# ESC.net
KiCad netlist of a schematic drawn in Altium Designer
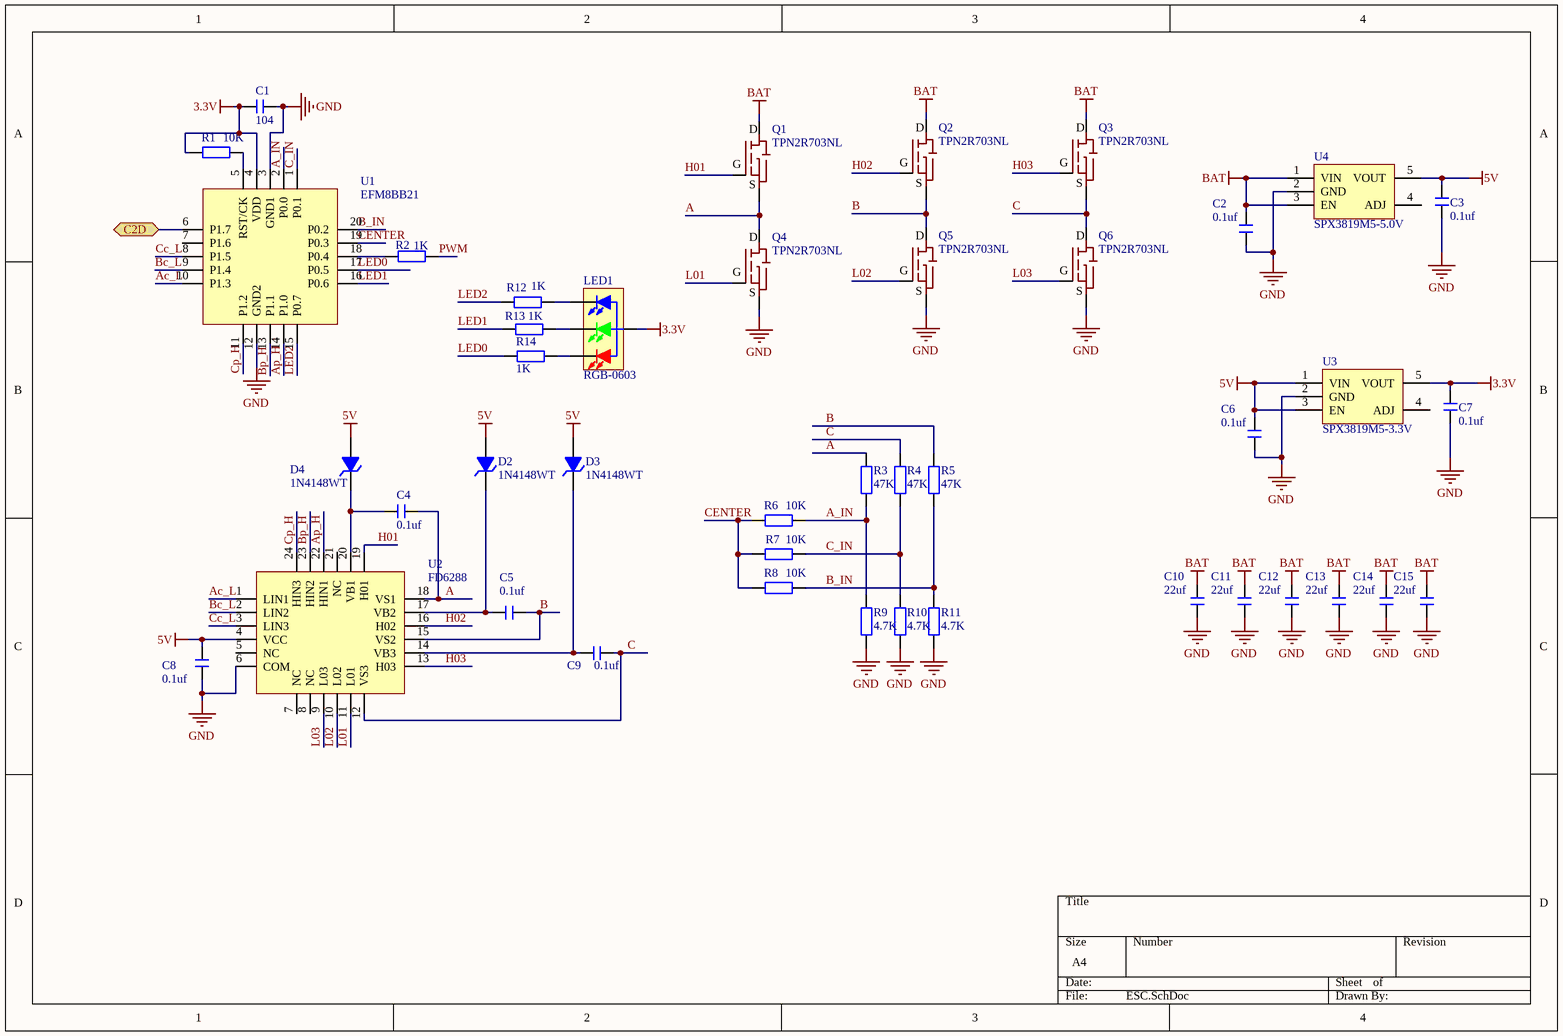
[diagram p0: ESC.SchDoc]

(export (version "E")
  (design (tool "Eeschema 10.0.6"))
  (components
    (comp (ref "C1")
      (value "104")
      (footprint "0402-C-1.6*0.5")
      (description "无极性贴片电容")
      (fields (field (name "版权归属") "源创客"))
      (libsource (lib "3.1   - 电阻-电容-电感") (part "C"))
    )
    (comp (ref "C2") (value "0.1uf") (footprint "0402-C-1.6*0.5") (libsource (lib "L-电阻电容电感") (part "C")))
    (comp (ref "C3") (value "0.1uf") (footprint "0402-C-1.6*0.5") (libsource (lib "L-电阻电容电感") (part "C")))
    (comp (ref "C4") (value "0.1uf") (footprint "0402-C-1.6*0.5") (libsource (lib "L-电阻电容电感") (part "C")))
    (comp (ref "C5") (value "0.1uf") (footprint "0402-C-1.6*0.5") (libsource (lib "L-电阻电容电感") (part "C")))
    (comp (ref "C6") (value "0.1uf") (footprint "0402-C-1.6*0.5") (libsource (lib "L-电阻电容电感") (part "C")))
    (comp (ref "C7") (value "0.1uf") (footprint "0402-C-1.6*0.5") (libsource (lib "L-电阻电容电感") (part "C")))
    (comp (ref "C8") (value "0.1uf") (footprint "0402-C-1.6*0.5") (libsource (lib "L-电阻电容电感") (part "C")))
    (comp (ref "C9") (value "0.1uf") (footprint "0402-C-1.6*0.5") (libsource (lib "L-电阻电容电感") (part "C")))
    (comp (ref "C10") (value "22uf") (footprint "0805-C-3.0*1.4") (libsource (lib "L-电阻电容电感") (part "C")))
    (comp (ref "C11") (value "22uf") (footprint "0805-C-3.0*1.4") (libsource (lib "L-电阻电容电感") (part "C")))
    (comp (ref "C12") (value "22uf") (footprint "0805-C-3.0*1.4") (libsource (lib "L-电阻电容电感") (part "C")))
    (comp (ref "C13") (value "22uf") (footprint "0805-C-3.0*1.4") (libsource (lib "L-电阻电容电感") (part "C")))
    (comp (ref "C14") (value "22uf") (footprint "0805-C-3.0*1.4") (libsource (lib "L-电阻电容电感") (part "C")))
    (comp (ref "C15") (value "22uf") (footprint "0805-C-3.0*1.4") (libsource (lib "L-电阻电容电感") (part "C")))
    (comp (ref "D2")
      (value "1N4148WT")
      (footprint "L_SOD523")
      (libsource (lib "L-二极管、稳压管") (part "1N4148WT"))
    )
    (comp (ref "D3")
      (value "1N4148WT")
      (footprint "L_SOD523")
      (libsource (lib "L-二极管、稳压管") (part "1N4148WT"))
    )
    (comp (ref "D4")
      (value "1N4148WT")
      (footprint "L_SOD523")
      (libsource (lib "L-二极管、稳压管") (part "1N4148WT"))
    )
    (comp (ref "LED1")
      (value "RGB-0603")
      (footprint "LC-0603_Rx2")
      (description "三基色LED")
      (fields (field (name "版权归属") "源创客"))
      (libsource (lib "9.1   - LED") (part "LED-RGB-3528"))
    )
    (comp (ref "Q1")
      (value "TPN2R703NL")
      (footprint "8-PowerVDFN")
      (libsource (lib "L-MOSFET") (part "TPN2R703NL"))
    )
    (comp (ref "Q2")
      (value "TPN2R703NL")
      (footprint "8-PowerVDFN")
      (libsource (lib "L-MOSFET") (part "TPN2R703NL"))
    )
    (comp (ref "Q3")
      (value "TPN2R703NL")
      (footprint "8-PowerVDFN")
      (libsource (lib "L-MOSFET") (part "TPN2R703NL"))
    )
    (comp (ref "Q4")
      (value "TPN2R703NL")
      (footprint "8-PowerVDFN")
      (libsource (lib "L-MOSFET") (part "TPN2R703NL"))
    )
    (comp (ref "Q5")
      (value "TPN2R703NL")
      (footprint "8-PowerVDFN")
      (libsource (lib "L-MOSFET") (part "TPN2R703NL"))
    )
    (comp (ref "Q6")
      (value "TPN2R703NL")
      (footprint "8-PowerVDFN")
      (libsource (lib "L-MOSFET") (part "TPN2R703NL"))
    )
    (comp (ref "R1") (value "10K") (footprint "0402-R-1.6*0.5") (libsource (lib "L-电阻电容电感") (part "R")))
    (comp (ref "R2")
      (value "1K")
      (footprint "0402-R-1.6*0.5")
      (description "贴片电阻")
      (fields (field (name "版权归属") "源创客"))
      (libsource (lib "3.1   - 电阻-电容-电感") (part "R"))
    )
    (comp (ref "R3") (value "47K") (footprint "0402-R-1.6*0.5") (libsource (lib "L-电阻电容电感") (part "R")))
    (comp (ref "R4") (value "47K") (footprint "0402-R-1.6*0.5") (libsource (lib "L-电阻电容电感") (part "R")))
    (comp (ref "R5") (value "47K") (footprint "0402-R-1.6*0.5") (libsource (lib "L-电阻电容电感") (part "R")))
    (comp (ref "R6") (value "10K") (footprint "0402-R-1.6*0.5") (libsource (lib "L-电阻电容电感") (part "R")))
    (comp (ref "R7") (value "10K") (footprint "0402-R-1.6*0.5") (libsource (lib "L-电阻电容电感") (part "R")))
    (comp (ref "R8") (value "10K") (footprint "0402-R-1.6*0.5") (libsource (lib "L-电阻电容电感") (part "R")))
    (comp (ref "R9") (value "4.7K") (footprint "0402-R-1.6*0.5") (libsource (lib "L-电阻电容电感") (part "R")))
    (comp (ref "R10") (value "4.7K") (footprint "0402-R-1.6*0.5") (libsource (lib "L-电阻电容电感") (part "R")))
    (comp (ref "R11") (value "4.7K") (footprint "0402-R-1.6*0.5") (libsource (lib "L-电阻电容电感") (part "R")))
    (comp (ref "R12") (value "1K") (footprint "0402-R-1.6*0.5") (libsource (lib "PCB_Project3") (part "R")))
    (comp (ref "R13") (value "1K") (footprint "0402-R-1.6*0.5") (libsource (lib "PCB_Project3") (part "R")))
    (comp (ref "R14") (value "1K") (footprint "0402-R-1.6*0.5") (libsource (lib "PCB_Project3") (part "R")))
    (comp (ref "U1")
      (value "EFM8BB21")
      (footprint "EFM8BB21F16G-C-QFN20")
      (libsource (lib "PCB_Project3") (part "EFM8BB21"))
    )
    (comp (ref "U2")
      (value "FD6288")
      (footprint "LC-QFN-24_4x4x05P")
      (libsource (lib "PCB_Project3") (part "FD6288"))
    )
    (comp (ref "U3")
      (value "SPX3819M5-3.3V")
      (footprint "L - SOT23-5L")
      (fields (field (name "版权所有") "Ly"))
      (libsource (lib "L-电源芯片") (part "SPX3819M5"))
    )
    (comp (ref "U4")
      (value "SPX3819M5-5.0V")
      (footprint "L - SOT23-5L")
      (fields (field (name "版权所有") "Ly"))
      (libsource (lib "L-电源芯片") (part "SPX3819M5"))
    )
  )
  (nets
    (net (code "1") (name "/A") (class "Default")
      (node (ref "C4") (pin "2") (pinfunction "2_2") (pintype "passive"))
      (node (ref "Q1") (pin "1") (pinfunction "1_1") (pintype "passive"))
      (node (ref "Q4") (pin "3") (pinfunction "3_3") (pintype "passive"))
      (node (ref "R3") (pin "1") (pinfunction "1_1") (pintype "passive"))
      (node (ref "U2") (pin "18") (pinfunction "VS1_18") (pintype "passive"))
    )
    (net (code "2") (name "/A_IN") (class "Default")
      (node (ref "R3") (pin "2") (pinfunction "2_2") (pintype "passive"))
      (node (ref "R6") (pin "2") (pinfunction "2_2") (pintype "passive"))
      (node (ref "R9") (pin "1") (pinfunction "1_1") (pintype "passive"))
      (node (ref "U1") (pin "2") (pinfunction "P0.0_2") (pintype "passive"))
    )
    (net (code "3") (name "/Ac_L") (class "Default")
      (node (ref "U1") (pin "10") (pinfunction "P1.3_10") (pintype "passive"))
      (node (ref "U2") (pin "1") (pinfunction "LIN1_1") (pintype "passive"))
    )
    (net (code "4") (name "/Ap_H") (class "Default")
      (node (ref "U1") (pin "14") (pinfunction "P1.0_14") (pintype "passive"))
      (node (ref "U2") (pin "22") (pinfunction "HIN1_22") (pintype "passive"))
    )
    (net (code "5") (name "/B") (class "Default")
      (node (ref "C5") (pin "2") (pinfunction "2_2") (pintype "passive"))
      (node (ref "Q2") (pin "1") (pinfunction "1_1") (pintype "passive"))
      (node (ref "Q5") (pin "3") (pinfunction "3_3") (pintype "passive"))
      (node (ref "R5") (pin "1") (pinfunction "1_1") (pintype "passive"))
      (node (ref "U2") (pin "15") (pinfunction "VS2_15") (pintype "passive"))
    )
    (net (code "6") (name "/B_IN") (class "Default")
      (node (ref "R11") (pin "1") (pinfunction "1_1") (pintype "passive"))
      (node (ref "R5") (pin "2") (pinfunction "2_2") (pintype "passive"))
      (node (ref "R8") (pin "2") (pinfunction "2_2") (pintype "passive"))
      (node (ref "U1") (pin "20") (pinfunction "P0.2_20") (pintype "passive"))
    )
    (net (code "7") (name "/Bc_L") (class "Default")
      (node (ref "U1") (pin "9") (pinfunction "P1.4_9") (pintype "passive"))
      (node (ref "U2") (pin "2") (pinfunction "LIN2_2") (pintype "passive"))
    )
    (net (code "8") (name "/Bp_H") (class "Default")
      (node (ref "U1") (pin "13") (pinfunction "P1.1_13") (pintype "passive"))
      (node (ref "U2") (pin "23") (pinfunction "HIN2_23") (pintype "passive"))
    )
    (net (code "9") (name "/C") (class "Default")
      (node (ref "C9") (pin "2") (pinfunction "2_2") (pintype "passive"))
      (node (ref "Q3") (pin "1") (pinfunction "1_1") (pintype "passive"))
      (node (ref "Q6") (pin "3") (pinfunction "3_3") (pintype "passive"))
      (node (ref "R4") (pin "1") (pinfunction "1_1") (pintype "passive"))
      (node (ref "U2") (pin "12") (pinfunction "VS3_12") (pintype "passive"))
    )
    (net (code "10") (name "/C2D") (class "Default")
      (node (ref "U1") (pin "6") (pinfunction "P1.7_6") (pintype "passive"))
    )
    (net (code "11") (name "/CENTER") (class "Default")
      (node (ref "R6") (pin "1") (pinfunction "1_1") (pintype "passive"))
      (node (ref "R7") (pin "1") (pinfunction "1_1") (pintype "passive"))
      (node (ref "R8") (pin "1") (pinfunction "1_1") (pintype "passive"))
      (node (ref "U1") (pin "19") (pinfunction "P0.3_19") (pintype "passive"))
    )
    (net (code "12") (name "/C_IN") (class "Default")
      (node (ref "R10") (pin "1") (pinfunction "1_1") (pintype "passive"))
      (node (ref "R4") (pin "2") (pinfunction "2_2") (pintype "passive"))
      (node (ref "R7") (pin "2") (pinfunction "2_2") (pintype "passive"))
      (node (ref "U1") (pin "1") (pinfunction "P0.1_1") (pintype "passive"))
    )
    (net (code "13") (name "/Cc_L") (class "Default")
      (node (ref "U1") (pin "8") (pinfunction "P1.5_8") (pintype "passive"))
      (node (ref "U2") (pin "3") (pinfunction "LIN3_3") (pintype "passive"))
    )
    (net (code "14") (name "/Cp_H") (class "Default")
      (node (ref "U1") (pin "11") (pinfunction "P1.2_11") (pintype "passive"))
      (node (ref "U2") (pin "24") (pinfunction "HIN3_24") (pintype "passive"))
    )
    (net (code "15") (name "/H01") (class "Default")
      (node (ref "Q1") (pin "2") (pinfunction "2_2") (pintype "passive"))
      (node (ref "U2") (pin "19") (pinfunction "H01_19") (pintype "passive"))
    )
    (net (code "16") (name "/H02") (class "Default")
      (node (ref "Q2") (pin "2") (pinfunction "2_2") (pintype "passive"))
      (node (ref "U2") (pin "16") (pinfunction "H02_16") (pintype "passive"))
    )
    (net (code "17") (name "/H03") (class "Default")
      (node (ref "Q3") (pin "2") (pinfunction "2_2") (pintype "passive"))
      (node (ref "U2") (pin "13") (pinfunction "H03_13") (pintype "passive"))
    )
    (net (code "18") (name "/L01") (class "Default")
      (node (ref "Q4") (pin "2") (pinfunction "2_2") (pintype "passive"))
      (node (ref "U2") (pin "11") (pinfunction "L01_11") (pintype "passive"))
    )
    (net (code "19") (name "/L02") (class "Default")
      (node (ref "Q5") (pin "2") (pinfunction "2_2") (pintype "passive"))
      (node (ref "U2") (pin "10") (pinfunction "L02_10") (pintype "passive"))
    )
    (net (code "20") (name "/L03") (class "Default")
      (node (ref "Q6") (pin "2") (pinfunction "2_2") (pintype "passive"))
      (node (ref "U2") (pin "9") (pinfunction "L03_9") (pintype "passive"))
    )
    (net (code "21") (name "/LED0") (class "Default")
      (node (ref "R14") (pin "1") (pinfunction "1_1") (pintype "passive"))
      (node (ref "U1") (pin "17") (pinfunction "P0.5_17") (pintype "passive"))
    )
    (net (code "22") (name "/LED1") (class "Default")
      (node (ref "R13") (pin "1") (pinfunction "1_1") (pintype "passive"))
      (node (ref "U1") (pin "16") (pinfunction "P0.6_16") (pintype "passive"))
    )
    (net (code "23") (name "/LED2") (class "Default")
      (node (ref "R12") (pin "1") (pinfunction "1_1") (pintype "passive"))
      (node (ref "U1") (pin "15") (pinfunction "P0.7_15") (pintype "passive"))
    )
    (net (code "24") (name "/PWM") (class "Default")
      (node (ref "R2") (pin "1") (pinfunction "1_1") (pintype "passive"))
    )
    (net (code "25") (name "3.3V") (class "Default")
      (node (ref "C1") (pin "2") (pinfunction "2_2") (pintype "passive"))
      (node (ref "C7") (pin "2") (pinfunction "2_2") (pintype "passive"))
      (node (ref "LED1") (pin "4") (pinfunction "A_4") (pintype "passive"))
      (node (ref "R1") (pin "1") (pinfunction "1_1") (pintype "passive"))
      (node (ref "U1") (pin "4") (pinfunction "VDD_4") (pintype "passive"))
      (node (ref "U3") (pin "5") (pinfunction "VOUT_5") (pintype "passive"))
    )
    (net (code "26") (name "5V") (class "Default")
      (node (ref "C3") (pin "2") (pinfunction "2_2") (pintype "passive"))
      (node (ref "C6") (pin "2") (pinfunction "2_2") (pintype "passive"))
      (node (ref "C8") (pin "2") (pinfunction "2_2") (pintype "passive"))
      (node (ref "D2") (pin "1") (pinfunction "A_1") (pintype "passive"))
      (node (ref "D3") (pin "1") (pinfunction "A_1") (pintype "passive"))
      (node (ref "D4") (pin "1") (pinfunction "A_1") (pintype "passive"))
      (node (ref "U2") (pin "4") (pinfunction "VCC_4") (pintype "passive"))
      (node (ref "U3") (pin "1") (pinfunction "VIN_1") (pintype "passive"))
      (node (ref "U3") (pin "3") (pinfunction "EN_3") (pintype "passive"))
      (node (ref "U4") (pin "5") (pinfunction "VOUT_5") (pintype "passive"))
    )
    (net (code "27") (name "BAT") (class "Default")
      (node (ref "C10") (pin "2") (pinfunction "2_2") (pintype "passive"))
      (node (ref "C11") (pin "2") (pinfunction "2_2") (pintype "passive"))
      (node (ref "C12") (pin "2") (pinfunction "2_2") (pintype "passive"))
      (node (ref "C13") (pin "2") (pinfunction "2_2") (pintype "passive"))
      (node (ref "C14") (pin "2") (pinfunction "2_2") (pintype "passive"))
      (node (ref "C15") (pin "2") (pinfunction "2_2") (pintype "passive"))
      (node (ref "C2") (pin "2") (pinfunction "2_2") (pintype "passive"))
      (node (ref "Q1") (pin "3") (pinfunction "3_3") (pintype "passive"))
      (node (ref "Q2") (pin "3") (pinfunction "3_3") (pintype "passive"))
      (node (ref "Q3") (pin "3") (pinfunction "3_3") (pintype "passive"))
      (node (ref "U4") (pin "1") (pinfunction "VIN_1") (pintype "passive"))
      (node (ref "U4") (pin "3") (pinfunction "EN_3") (pintype "passive"))
    )
    (net (code "28") (name "GND") (class "Default")
      (node (ref "C1") (pin "1") (pinfunction "1_1") (pintype "passive"))
      (node (ref "C10") (pin "1") (pinfunction "1_1") (pintype "passive"))
      (node (ref "C11") (pin "1") (pinfunction "1_1") (pintype "passive"))
      (node (ref "C12") (pin "1") (pinfunction "1_1") (pintype "passive"))
      (node (ref "C13") (pin "1") (pinfunction "1_1") (pintype "passive"))
      (node (ref "C14") (pin "1") (pinfunction "1_1") (pintype "passive"))
      (node (ref "C15") (pin "1") (pinfunction "1_1") (pintype "passive"))
      (node (ref "C2") (pin "1") (pinfunction "1_1") (pintype "passive"))
      (node (ref "C3") (pin "1") (pinfunction "1_1") (pintype "passive"))
      (node (ref "C6") (pin "1") (pinfunction "1_1") (pintype "passive"))
      (node (ref "C7") (pin "1") (pinfunction "1_1") (pintype "passive"))
      (node (ref "C8") (pin "1") (pinfunction "1_1") (pintype "passive"))
      (node (ref "Q4") (pin "1") (pinfunction "1_1") (pintype "passive"))
      (node (ref "Q5") (pin "1") (pinfunction "1_1") (pintype "passive"))
      (node (ref "Q6") (pin "1") (pinfunction "1_1") (pintype "passive"))
      (node (ref "R10") (pin "2") (pinfunction "2_2") (pintype "passive"))
      (node (ref "R11") (pin "2") (pinfunction "2_2") (pintype "passive"))
      (node (ref "R9") (pin "2") (pinfunction "2_2") (pintype "passive"))
      (node (ref "U1") (pin "12") (pinfunction "GND2_12") (pintype "passive"))
      (node (ref "U1") (pin "3") (pinfunction "GND1_3") (pintype "passive"))
      (node (ref "U2") (pin "6") (pinfunction "COM_6") (pintype "passive"))
      (node (ref "U3") (pin "2") (pinfunction "GND_2") (pintype "passive"))
      (node (ref "U4") (pin "2") (pinfunction "GND_2") (pintype "passive"))
    )
    (net (code "29") (name "Net-(D2-K)") (class "Default")
      (node (ref "C5") (pin "1") (pinfunction "1_1") (pintype "passive"))
      (node (ref "D2") (pin "2") (pinfunction "K_2") (pintype "passive"))
      (node (ref "U2") (pin "17") (pinfunction "VB2_17") (pintype "passive"))
    )
    (net (code "30") (name "Net-(D3-K)") (class "Default")
      (node (ref "C9") (pin "1") (pinfunction "1_1") (pintype "passive"))
      (node (ref "D3") (pin "2") (pinfunction "K_2") (pintype "passive"))
      (node (ref "U2") (pin "14") (pinfunction "VB3_14") (pintype "passive"))
    )
    (net (code "31") (name "Net-(D4-K)") (class "Default")
      (node (ref "C4") (pin "1") (pinfunction "1_1") (pintype "passive"))
      (node (ref "D4") (pin "2") (pinfunction "K_2") (pintype "passive"))
      (node (ref "U2") (pin "20") (pinfunction "VB1_20") (pintype "passive"))
    )
    (net (code "32") (name "Net-(LED1-BULE_K)") (class "Default")
      (node (ref "LED1") (pin "3") (pinfunction "BULE_K_3") (pintype "passive"))
      (node (ref "R12") (pin "2") (pinfunction "2_2") (pintype "passive"))
    )
    (net (code "33") (name "Net-(LED1-GREEN_K)") (class "Default")
      (node (ref "LED1") (pin "2") (pinfunction "GREEN_K_2") (pintype "passive"))
      (node (ref "R13") (pin "2") (pinfunction "2_2") (pintype "passive"))
    )
    (net (code "34") (name "Net-(LED1-RED_K)") (class "Default")
      (node (ref "LED1") (pin "1") (pinfunction "RED_K_1") (pintype "passive"))
      (node (ref "R14") (pin "2") (pinfunction "2_2") (pintype "passive"))
    )
    (net (code "35") (name "Net-(U1-P0.4)") (class "Default")
      (node (ref "R2") (pin "2") (pinfunction "2_2") (pintype "passive"))
      (node (ref "U1") (pin "18") (pinfunction "P0.4_18") (pintype "passive"))
    )
    (net (code "36") (name "Net-(U1-RST{slash}CK)") (class "Default")
      (node (ref "R1") (pin "2") (pinfunction "2_2") (pintype "passive"))
      (node (ref "U1") (pin "5") (pinfunction "RST/CK_5") (pintype "passive"))
    )
    (net (code "37") (name "unconnected-(U1-P1.6-Pad7)") (class "Default")
      (node (ref "U1") (pin "7") (pinfunction "P1.6_7") (pintype "passive"))
    )
    (net (code "38") (name "unconnected-(U2-NC-Pad5)") (class "Default")
      (node (ref "U2") (pin "5") (pinfunction "NC_5") (pintype "passive"))
    )
    (net (code "39") (name "unconnected-(U2-NC-Pad7)") (class "Default")
      (node (ref "U2") (pin "7") (pinfunction "NC_7") (pintype "passive"))
    )
    (net (code "40") (name "unconnected-(U2-NC-Pad8)") (class "Default")
      (node (ref "U2") (pin "8") (pinfunction "NC_8") (pintype "passive"))
    )
    (net (code "41") (name "unconnected-(U2-NC-Pad21)") (class "Default")
      (node (ref "U2") (pin "21") (pinfunction "NC_21") (pintype "passive"))
    )
    (net (code "42") (name "unconnected-(U3-ADJ-Pad4)") (class "Default")
      (node (ref "U3") (pin "4") (pinfunction "ADJ_4") (pintype "passive"))
    )
    (net (code "43") (name "unconnected-(U4-ADJ-Pad4)") (class "Default")
      (node (ref "U4") (pin "4") (pinfunction "ADJ_4") (pintype "passive"))
    )
  )
)
